# Adafruit_Verter_TPS63060_2A_BoostBuck.net
KiCad netlist of a schematic drawn in EAGLE
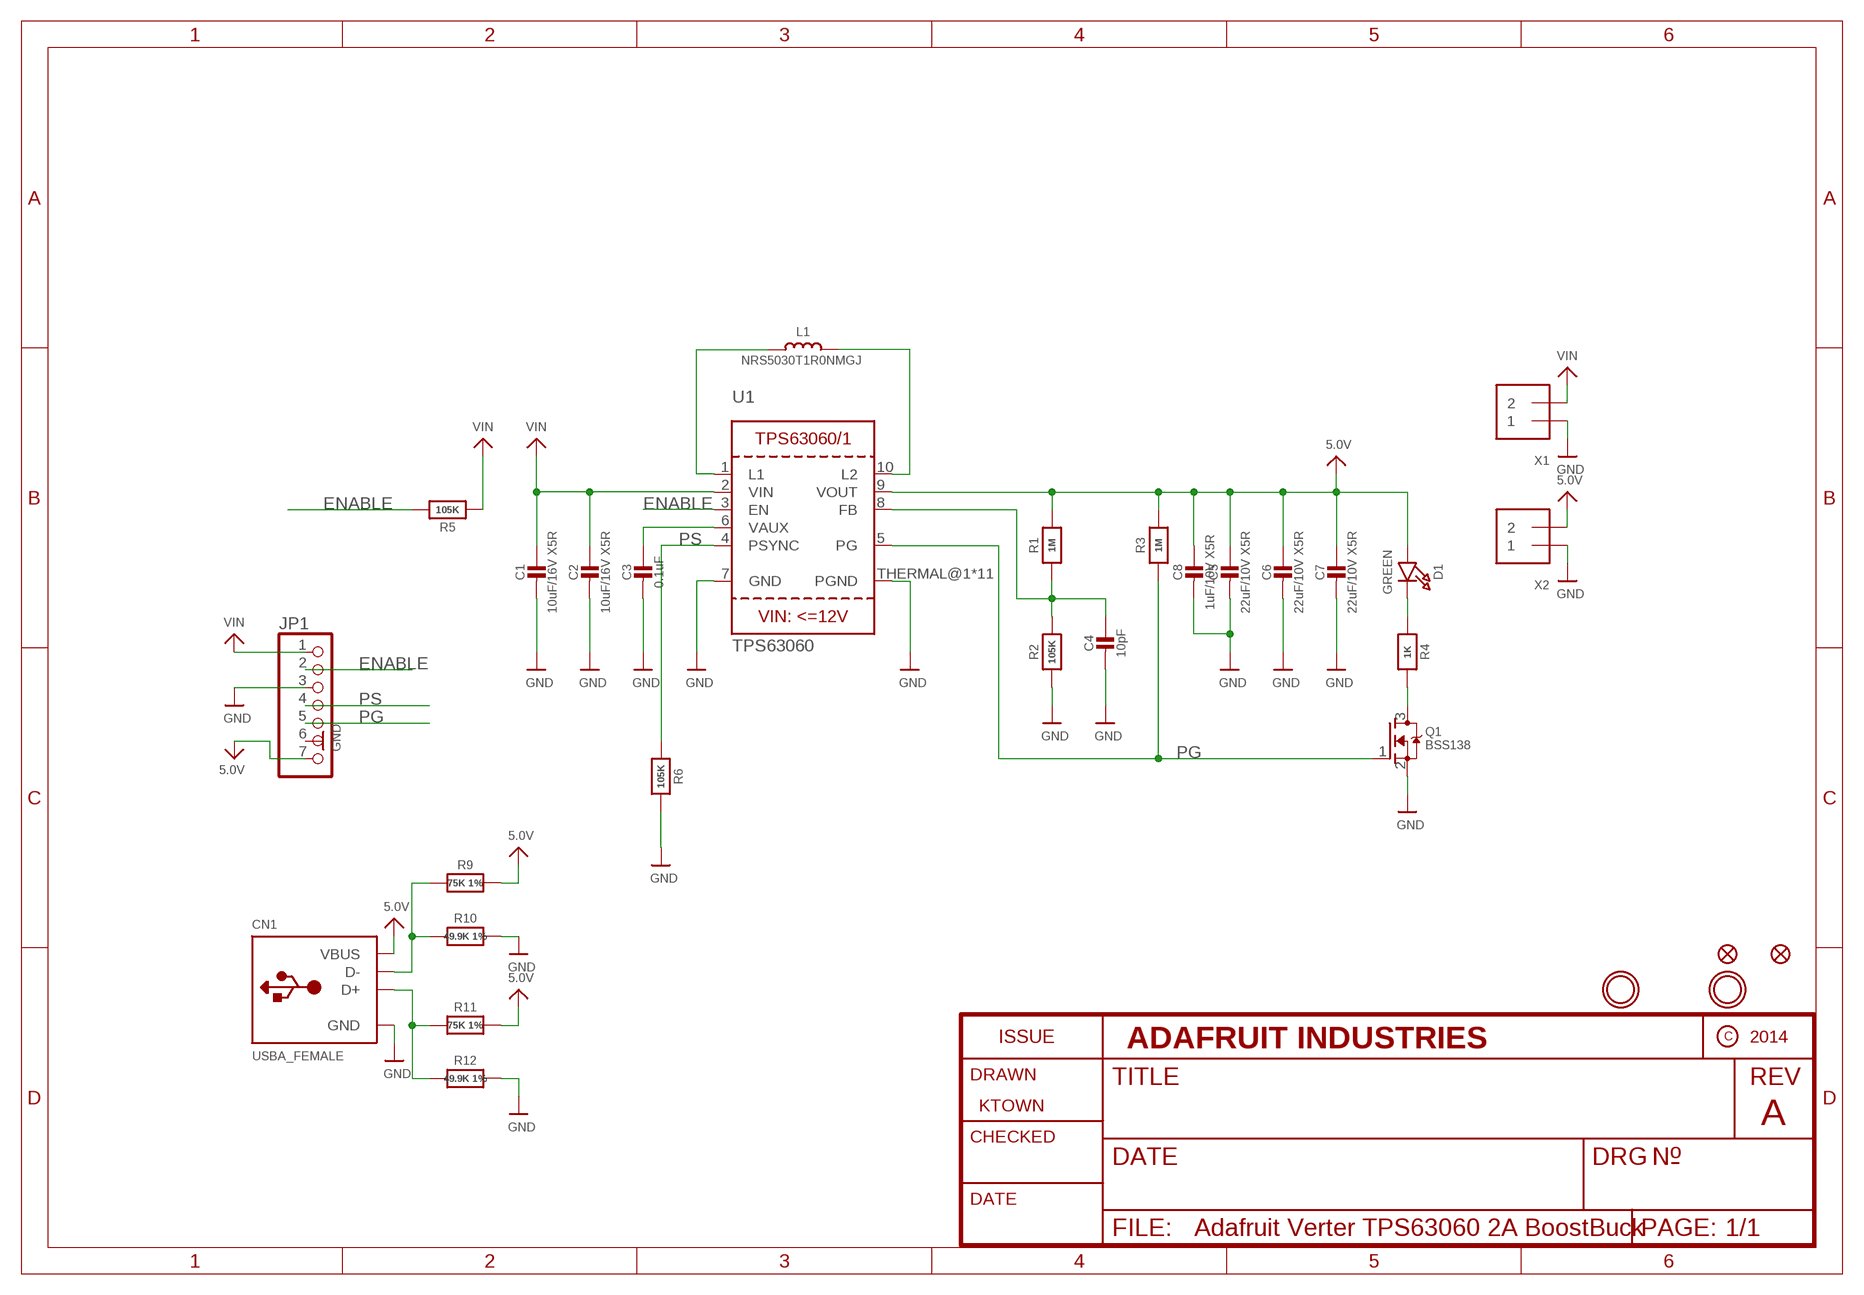
[diagram p0: schematic, sheet 1]

(export (version "E")
  (design (tool "Eeschema 10.0.6"))
  (components
    (comp (ref "C1")
      (value "10uF/16V X5R")
      (footprint "eagle-import:0805-NO")
      (libsource (lib "eagle-import") (part "CAP_CERAMIC0805-NOOUTLINE"))
    )
    (comp (ref "C2")
      (value "10uF/16V X5R")
      (footprint "eagle-import:0805-NO")
      (libsource (lib "eagle-import") (part "CAP_CERAMIC0805-NOOUTLINE"))
    )
    (comp (ref "C3")
      (value "0.1uF")
      (footprint "eagle-import:0805-NO")
      (libsource (lib "eagle-import") (part "CAP_CERAMIC0805-NOOUTLINE"))
    )
    (comp (ref "C4")
      (value "10pF")
      (footprint "eagle-import:0805-NO")
      (libsource (lib "eagle-import") (part "CAP_CERAMIC0805-NOOUTLINE"))
    )
    (comp (ref "C5")
      (value "22uF/10V X5R")
      (footprint "eagle-import:0805-NO")
      (libsource (lib "eagle-import") (part "CAP_CERAMIC0805-NOOUTLINE"))
    )
    (comp (ref "C6")
      (value "22uF/10V X5R")
      (footprint "eagle-import:0805-NO")
      (libsource (lib "eagle-import") (part "CAP_CERAMIC0805-NOOUTLINE"))
    )
    (comp (ref "C7")
      (value "22uF/10V X5R")
      (footprint "eagle-import:0805-NO")
      (libsource (lib "eagle-import") (part "CAP_CERAMIC0805-NOOUTLINE"))
    )
    (comp (ref "C8")
      (value "1uF/10V X5R")
      (footprint "eagle-import:0805-NO")
      (libsource (lib "eagle-import") (part "CAP_CERAMIC0805-NOOUTLINE"))
    )
    (comp (ref "CN1")
      (value "USBA_FEMALE")
      (footprint "eagle-import:USB_HOST-PTH")
      (libsource (lib "eagle-import") (part "USB_TYPEAPTHFML"))
    )
    (comp (ref "D1")
      (value "GREEN")
      (footprint "eagle-import:CHIPLED_0805_NOOUTLINE")
      (libsource (lib "eagle-import") (part "LED0805_NOOUTLINE"))
    )
    (comp (ref "FID1")
      (value "FIDUCIAL\"\"")
      (footprint "eagle-import:FIDUCIAL_1MM")
      (libsource (lib "eagle-import") (part "FIDUCIAL{dblquote}{dblquote}"))
    )
    (comp (ref "FID2")
      (value "FIDUCIAL\"\"")
      (footprint "eagle-import:FIDUCIAL_1MM")
      (libsource (lib "eagle-import") (part "FIDUCIAL{dblquote}{dblquote}"))
    )
    (comp (ref "JP1")
      (value "HEADER-1X770MIL")
      (footprint "eagle-import:1X07_ROUND_70")
      (libsource (lib "eagle-import") (part "HEADER-1X770MIL"))
    )
    (comp (ref "L1")
      (value "NRS5030T1R0NMGJ")
      (footprint "eagle-import:INDUCTOR_5X5MM_TDK_VLC5045")
      (libsource (lib "eagle-import") (part "INDUCTORTDK_VLC5045"))
    )
    (comp (ref "Q1")
      (value "BSS138")
      (footprint "eagle-import:SOT23-WIDE")
      (libsource (lib "eagle-import") (part "MOSFET-NWIDE"))
    )
    (comp (ref "R1")
      (value "1M")
      (footprint "eagle-import:0805-NO")
      (libsource (lib "eagle-import") (part "RESISTOR0805_NOOUTLINE"))
    )
    (comp (ref "R2")
      (value "105K")
      (footprint "eagle-import:0805-NO")
      (libsource (lib "eagle-import") (part "RESISTOR0805_NOOUTLINE"))
    )
    (comp (ref "R3")
      (value "1M")
      (footprint "eagle-import:0805-NO")
      (libsource (lib "eagle-import") (part "RESISTOR0805_NOOUTLINE"))
    )
    (comp (ref "R4")
      (value "1K")
      (footprint "eagle-import:0805-NO")
      (libsource (lib "eagle-import") (part "RESISTOR0805_NOOUTLINE"))
    )
    (comp (ref "R5")
      (value "105K")
      (footprint "eagle-import:0805-NO")
      (libsource (lib "eagle-import") (part "RESISTOR0805_NOOUTLINE"))
    )
    (comp (ref "R6")
      (value "105K")
      (footprint "eagle-import:0805-NO")
      (libsource (lib "eagle-import") (part "RESISTOR0805_NOOUTLINE"))
    )
    (comp (ref "R9")
      (value "75K 1%")
      (footprint "eagle-import:0805-NO")
      (libsource (lib "eagle-import") (part "RESISTOR0805_NOOUTLINE"))
    )
    (comp (ref "R10")
      (value "49.9K 1%")
      (footprint "eagle-import:0805-NO")
      (libsource (lib "eagle-import") (part "RESISTOR0805_NOOUTLINE"))
    )
    (comp (ref "R11")
      (value "75K 1%")
      (footprint "eagle-import:0805-NO")
      (libsource (lib "eagle-import") (part "RESISTOR0805_NOOUTLINE"))
    )
    (comp (ref "R12")
      (value "49.9K 1%")
      (footprint "eagle-import:0805-NO")
      (libsource (lib "eagle-import") (part "RESISTOR0805_NOOUTLINE"))
    )
    (comp (ref "U$15")
      (value "MOUNTINGHOLE2.5")
      (footprint "eagle-import:MOUNTINGHOLE_2.5_PLATED")
      (libsource (lib "eagle-import") (part "MOUNTINGHOLE2.5"))
    )
    (comp (ref "U$17")
      (value "MOUNTINGHOLE2.5")
      (footprint "eagle-import:MOUNTINGHOLE_2.5_PLATED")
      (libsource (lib "eagle-import") (part "MOUNTINGHOLE2.5"))
    )
    (comp (ref "U1")
      (value "TPS63060")
      (footprint "eagle-import:PWSON-N10")
      (libsource (lib "eagle-import") (part "VREG_TPS63060/1"))
    )
    (comp (ref "X1")
      (value "TERMBLOCK_1X2")
      (footprint "eagle-import:TERMBLOCK_1X2-3.5MM")
      (libsource (lib "eagle-import") (part "TERMBLOCK_1X2"))
    )
    (comp (ref "X2")
      (value "TERMBLOCK_1X2")
      (footprint "eagle-import:TERMBLOCK_1X2-3.5MM")
      (libsource (lib "eagle-import") (part "TERMBLOCK_1X2"))
    )
  )
  (nets
    (net (code "1") (name "/ENABLE") (class "Default")
      (node (ref "JP1") (pin "2") (pinfunction "2_2") (pintype "passive"))
      (node (ref "R5") (pin "2") (pinfunction "2_2") (pintype "passive"))
      (node (ref "U1") (pin "3") (pinfunction "EN_3") (pintype "input"))
    )
    (net (code "2") (name "/PG") (class "Default")
      (node (ref "JP1") (pin "5") (pinfunction "5_5") (pintype "passive"))
      (node (ref "Q1") (pin "1") (pinfunction "G_1") (pintype "bidirectional"))
      (node (ref "R3") (pin "1") (pinfunction "1_1") (pintype "passive"))
      (node (ref "U1") (pin "5") (pinfunction "PG_5") (pintype "open_collector"))
    )
    (net (code "3") (name "/PS") (class "Default")
      (node (ref "JP1") (pin "4") (pinfunction "4_4") (pintype "passive"))
      (node (ref "R6") (pin "1") (pinfunction "1_1") (pintype "passive"))
      (node (ref "U1") (pin "4") (pinfunction "PSYNC_4") (pintype "input"))
    )
    (net (code "4") (name "5.0V") (class "Default")
      (node (ref "C5") (pin "1") (pinfunction "1_1") (pintype "passive"))
      (node (ref "C6") (pin "1") (pinfunction "1_1") (pintype "passive"))
      (node (ref "C7") (pin "1") (pinfunction "1_1") (pintype "passive"))
      (node (ref "C8") (pin "1") (pinfunction "1_1") (pintype "passive"))
      (node (ref "CN1") (pin "VBUS") (pinfunction "VBUS_VBUS") (pintype "power_in"))
      (node (ref "D1") (pin "A") (pinfunction "A_A") (pintype "passive"))
      (node (ref "JP1") (pin "7") (pinfunction "7_7") (pintype "passive"))
      (node (ref "R1") (pin "2") (pinfunction "2_2") (pintype "passive"))
      (node (ref "R11") (pin "2") (pinfunction "2_2") (pintype "passive"))
      (node (ref "R3") (pin "2") (pinfunction "2_2") (pintype "passive"))
      (node (ref "R9") (pin "2") (pinfunction "2_2") (pintype "passive"))
      (node (ref "U1") (pin "9") (pinfunction "VOUT_9") (pintype "power_in"))
      (node (ref "X2") (pin "2") (pinfunction "2_2") (pintype "passive"))
    )
    (net (code "5") (name "GND") (class "Default")
      (node (ref "C1") (pin "2") (pinfunction "2_2") (pintype "passive"))
      (node (ref "C2") (pin "2") (pinfunction "2_2") (pintype "passive"))
      (node (ref "C3") (pin "2") (pinfunction "2_2") (pintype "passive"))
      (node (ref "C4") (pin "2") (pinfunction "2_2") (pintype "passive"))
      (node (ref "C5") (pin "2") (pinfunction "2_2") (pintype "passive"))
      (node (ref "C6") (pin "2") (pinfunction "2_2") (pintype "passive"))
      (node (ref "C7") (pin "2") (pinfunction "2_2") (pintype "passive"))
      (node (ref "C8") (pin "2") (pinfunction "2_2") (pintype "passive"))
      (node (ref "CN1") (pin "GND") (pinfunction "GND_GND") (pintype "power_in"))
      (node (ref "JP1") (pin "3") (pinfunction "3_3") (pintype "passive"))
      (node (ref "JP1") (pin "6") (pinfunction "6_6") (pintype "passive"))
      (node (ref "Q1") (pin "2") (pinfunction "S_2") (pintype "bidirectional"))
      (node (ref "R10") (pin "2") (pinfunction "2_2") (pintype "passive"))
      (node (ref "R12") (pin "2") (pinfunction "2_2") (pintype "passive"))
      (node (ref "R2") (pin "1") (pinfunction "1_1") (pintype "passive"))
      (node (ref "R6") (pin "2") (pinfunction "2_2") (pintype "passive"))
      (node (ref "U1") (pin "7") (pinfunction "GND_7") (pintype "power_in"))
      (node (ref "U1") (pin "THERMAL@1") (pinfunction "PGND_THERMAL@1") (pintype "power_in"))
      (node (ref "U1") (pin "THERMAL@10") (pinfunction "PGND_THERMAL@10") (pintype "power_in"))
      (node (ref "U1") (pin "THERMAL@11") (pinfunction "PGND_THERMAL@11") (pintype "power_in"))
      (node (ref "U1") (pin "THERMAL@12") (pinfunction "PGND_THERMAL@12") (pintype "power_in"))
      (node (ref "U1") (pin "THERMAL@13") (pinfunction "PGND_THERMAL@13") (pintype "power_in"))
      (node (ref "U1") (pin "THERMAL@14") (pinfunction "PGND_THERMAL@14") (pintype "power_in"))
      (node (ref "U1") (pin "THERMAL@5") (pinfunction "PGND_THERMAL@5") (pintype "power_in"))
      (node (ref "U1") (pin "THERMAL@6") (pinfunction "PGND_THERMAL@6") (pintype "power_in"))
      (node (ref "U1") (pin "THERMAL@7") (pinfunction "PGND_THERMAL@7") (pintype "power_in"))
      (node (ref "U1") (pin "THERMAL@8") (pinfunction "PGND_THERMAL@8") (pintype "power_in"))
      (node (ref "U1") (pin "THERMAL@9") (pinfunction "PGND_THERMAL@9") (pintype "power_in"))
      (node (ref "X1") (pin "1") (pinfunction "1_1") (pintype "passive"))
      (node (ref "X2") (pin "1") (pinfunction "1_1") (pintype "passive"))
    )
    (net (code "6") (name "Net-(CN1-PadD+)") (class "Default")
      (node (ref "CN1") (pin "D+") (pinfunction "D+_D+") (pintype "bidirectional"))
      (node (ref "R11") (pin "1") (pinfunction "1_1") (pintype "passive"))
      (node (ref "R12") (pin "1") (pinfunction "1_1") (pintype "passive"))
    )
    (net (code "7") (name "Net-(CN1-PadD-)") (class "Default")
      (node (ref "CN1") (pin "D-") (pinfunction "D-_D-") (pintype "bidirectional"))
      (node (ref "R10") (pin "1") (pinfunction "1_1") (pintype "passive"))
      (node (ref "R9") (pin "1") (pinfunction "1_1") (pintype "passive"))
    )
    (net (code "8") (name "Net-(D1-PadC)") (class "Default")
      (node (ref "D1") (pin "C") (pinfunction "C_C") (pintype "passive"))
      (node (ref "R4") (pin "1") (pinfunction "1_1") (pintype "passive"))
    )
    (net (code "9") (name "Net-(L1-1)") (class "Default")
      (node (ref "L1") (pin "P$1") (pinfunction "1_P$1") (pintype "passive"))
      (node (ref "U1") (pin "1") (pinfunction "L1_1") (pintype "input"))
    )
    (net (code "10") (name "Net-(L1-2)") (class "Default")
      (node (ref "L1") (pin "P$2") (pinfunction "2_P$2") (pintype "passive"))
      (node (ref "U1") (pin "10") (pinfunction "L2_10") (pintype "input"))
    )
    (net (code "11") (name "Net-(Q1-D)") (class "Default")
      (node (ref "Q1") (pin "3") (pinfunction "D_3") (pintype "bidirectional"))
      (node (ref "R4") (pin "2") (pinfunction "2_2") (pintype "passive"))
    )
    (net (code "12") (name "Net-(U1-FB)") (class "Default")
      (node (ref "C4") (pin "1") (pinfunction "1_1") (pintype "passive"))
      (node (ref "R1") (pin "1") (pinfunction "1_1") (pintype "passive"))
      (node (ref "R2") (pin "2") (pinfunction "2_2") (pintype "passive"))
      (node (ref "U1") (pin "8") (pinfunction "FB_8") (pintype "input"))
    )
    (net (code "13") (name "Net-(U1-VAUX)") (class "Default")
      (node (ref "C3") (pin "1") (pinfunction "1_1") (pintype "passive"))
      (node (ref "U1") (pin "6") (pinfunction "VAUX_6") (pintype "passive"))
    )
    (net (code "14") (name "VIN") (class "Default")
      (node (ref "C1") (pin "1") (pinfunction "1_1") (pintype "passive"))
      (node (ref "C2") (pin "1") (pinfunction "1_1") (pintype "passive"))
      (node (ref "JP1") (pin "1") (pinfunction "1_1") (pintype "passive"))
      (node (ref "R5") (pin "1") (pinfunction "1_1") (pintype "passive"))
      (node (ref "U1") (pin "2") (pinfunction "VIN_2") (pintype "power_in"))
      (node (ref "X1") (pin "2") (pinfunction "2_2") (pintype "passive"))
    )
  )
)
